# PLD_Top.net
KiCad netlist of a schematic drawn in Altium Designer
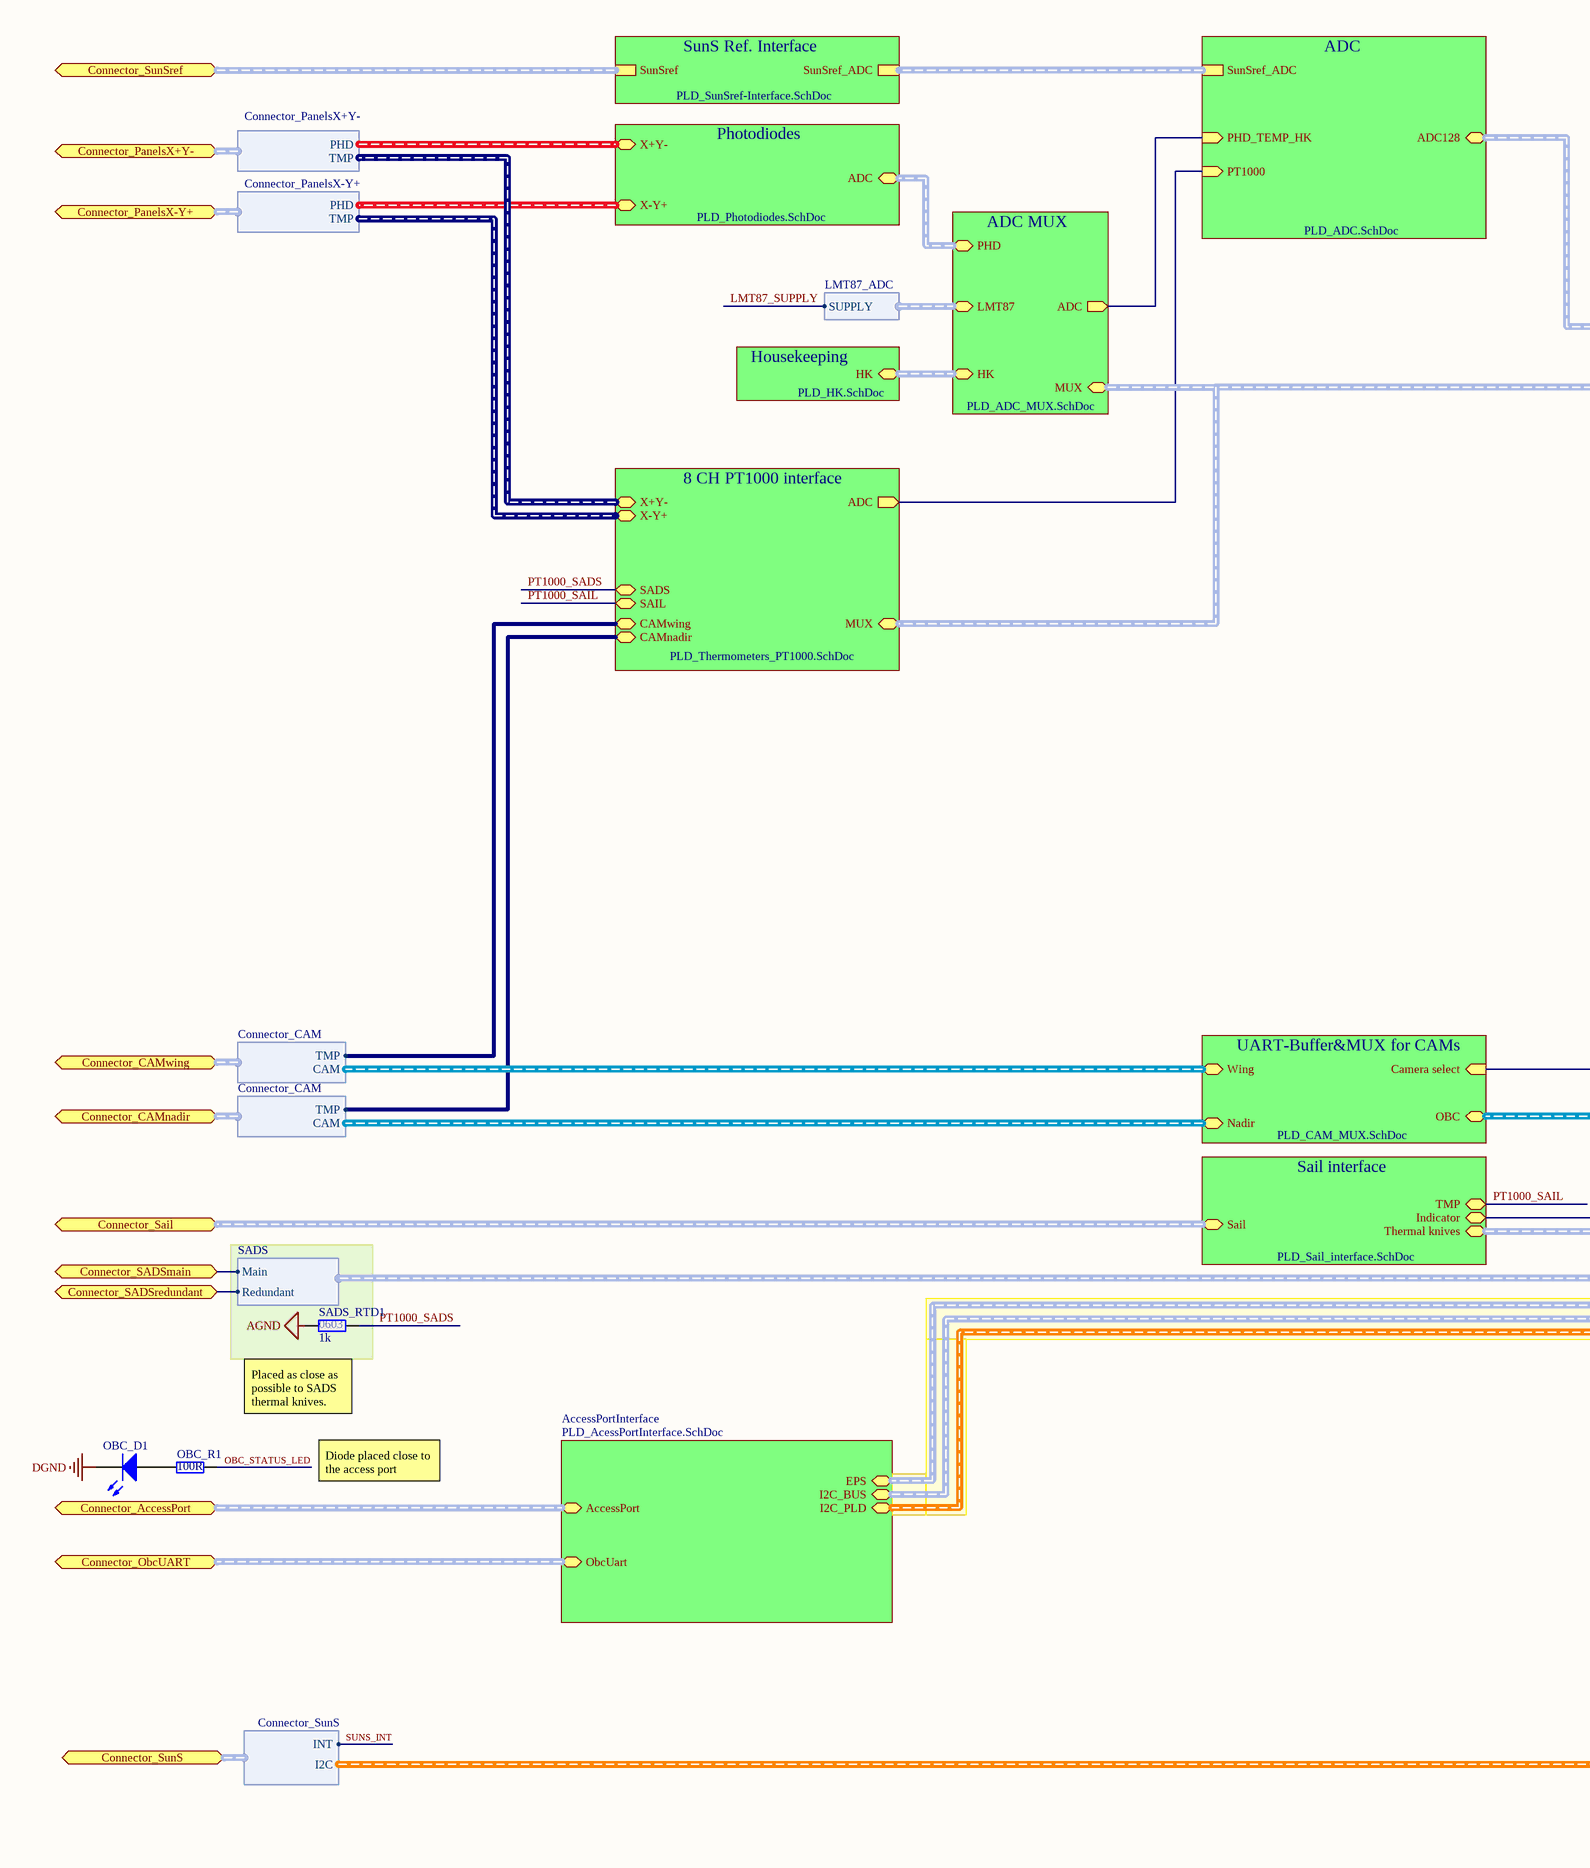
[diagram p0: PLD_Top.SchDoc, left]
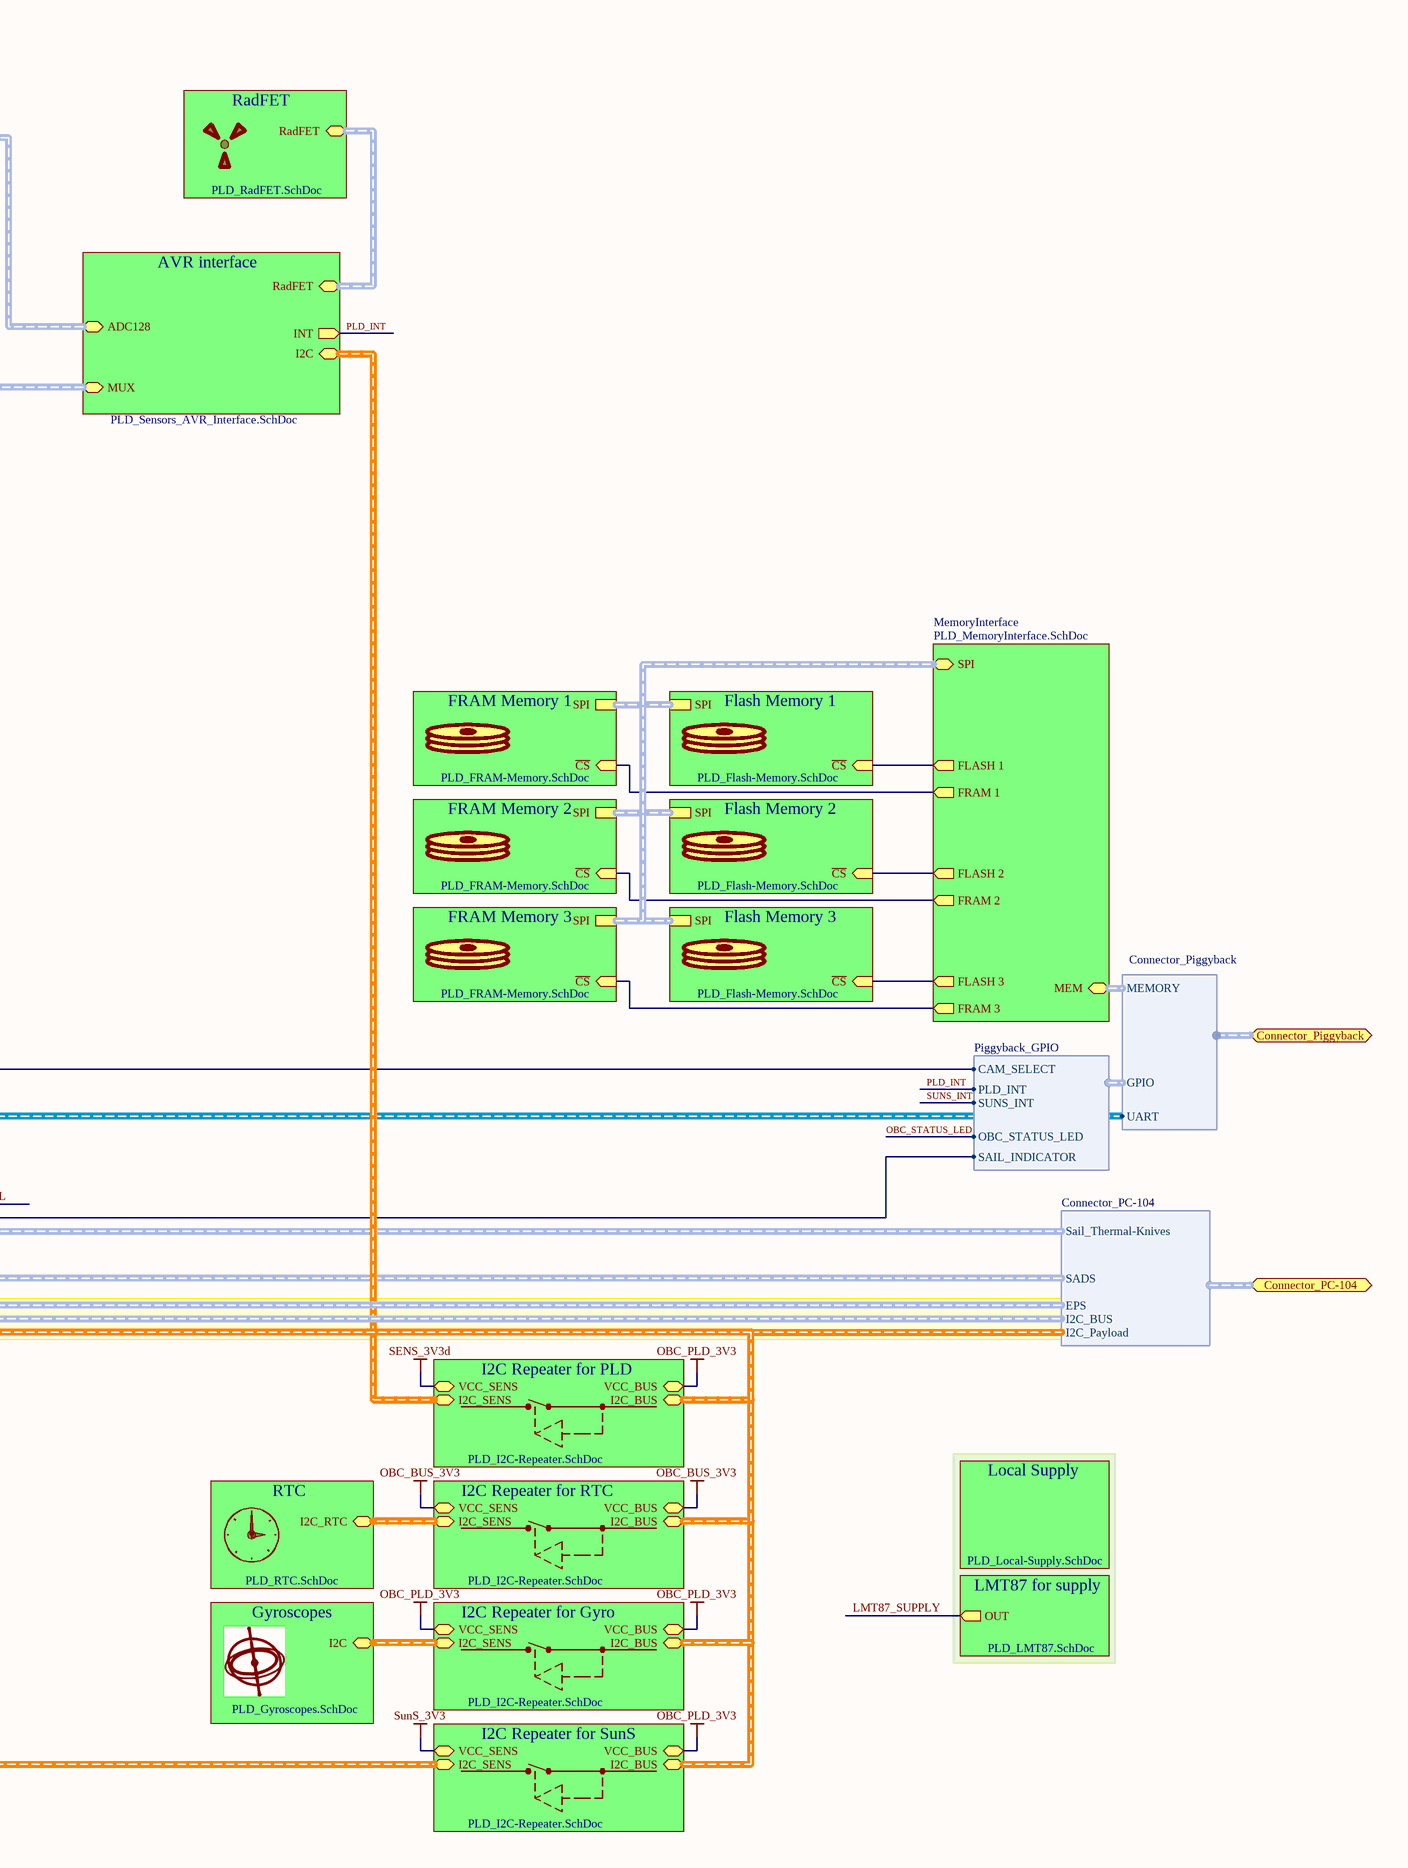
[diagram p1: PLD_Top.SchDoc, right]

(export (version "E")
  (design (tool "Eeschema 10.0.6"))
  (components
    (comp (ref "OBC_D1")
      (value "LEDX")
      (footprint "LED 0805 Blue")
      (description "Typical LED")
      (libsource (lib "diodes") (part "LEDX"))
    )
    (comp (ref "OBC_R1")
      (value "100R")
      (footprint "SMD_Resistor_0603")
      (libsource (lib "resistors") (part "Res"))
    )
    (comp (ref "SADS_RTD1")
      (value "1k")
      (footprint "SMD_Resistor_0603")
      (description "PT1000 Vishay PTS060301B100RP100")
      (fields
        (field (name "MANUFACTURER") "Vishay")
        (field (name "MANUFACTURERPARTNUMBER") "PTS060301B100RP100")
        (field (name "PACKAGE") "0603")
      )
      (libsource (lib "resistors") (part "PTS060301B100RP100"))
    )
  )
  (nets
    (net (code "54") (name "/OBC_STATUS_LED") (class "Default")
      (node (ref "OBC_R1") (pin "2") (pinfunction "2_2") (pintype "passive"))
    )
    (net (code "56") (name "/PT1000_SADS") (class "Default")
      (node (ref "SADS_RTD1") (pin "2") (pinfunction "2_2") (pintype "passive"))
    )
    (net (code "71") (name "AGND") (class "Default")
      (node (ref "SADS_RTD1") (pin "1") (pinfunction "1_1") (pintype "passive"))
    )
    (net (code "72") (name "DGND") (class "Default")
      (node (ref "OBC_D1") (pin "2") (pinfunction "K_2") (pintype "passive"))
    )
    (net (code "73") (name "Net-(OBC_D1-A)") (class "Default")
      (node (ref "OBC_D1") (pin "1") (pinfunction "A_1") (pintype "passive"))
      (node (ref "OBC_R1") (pin "1") (pinfunction "1_1") (pintype "passive"))
    )
  )
)
